# SCH.net
KiCad netlist of a schematic drawn in EasyEDA
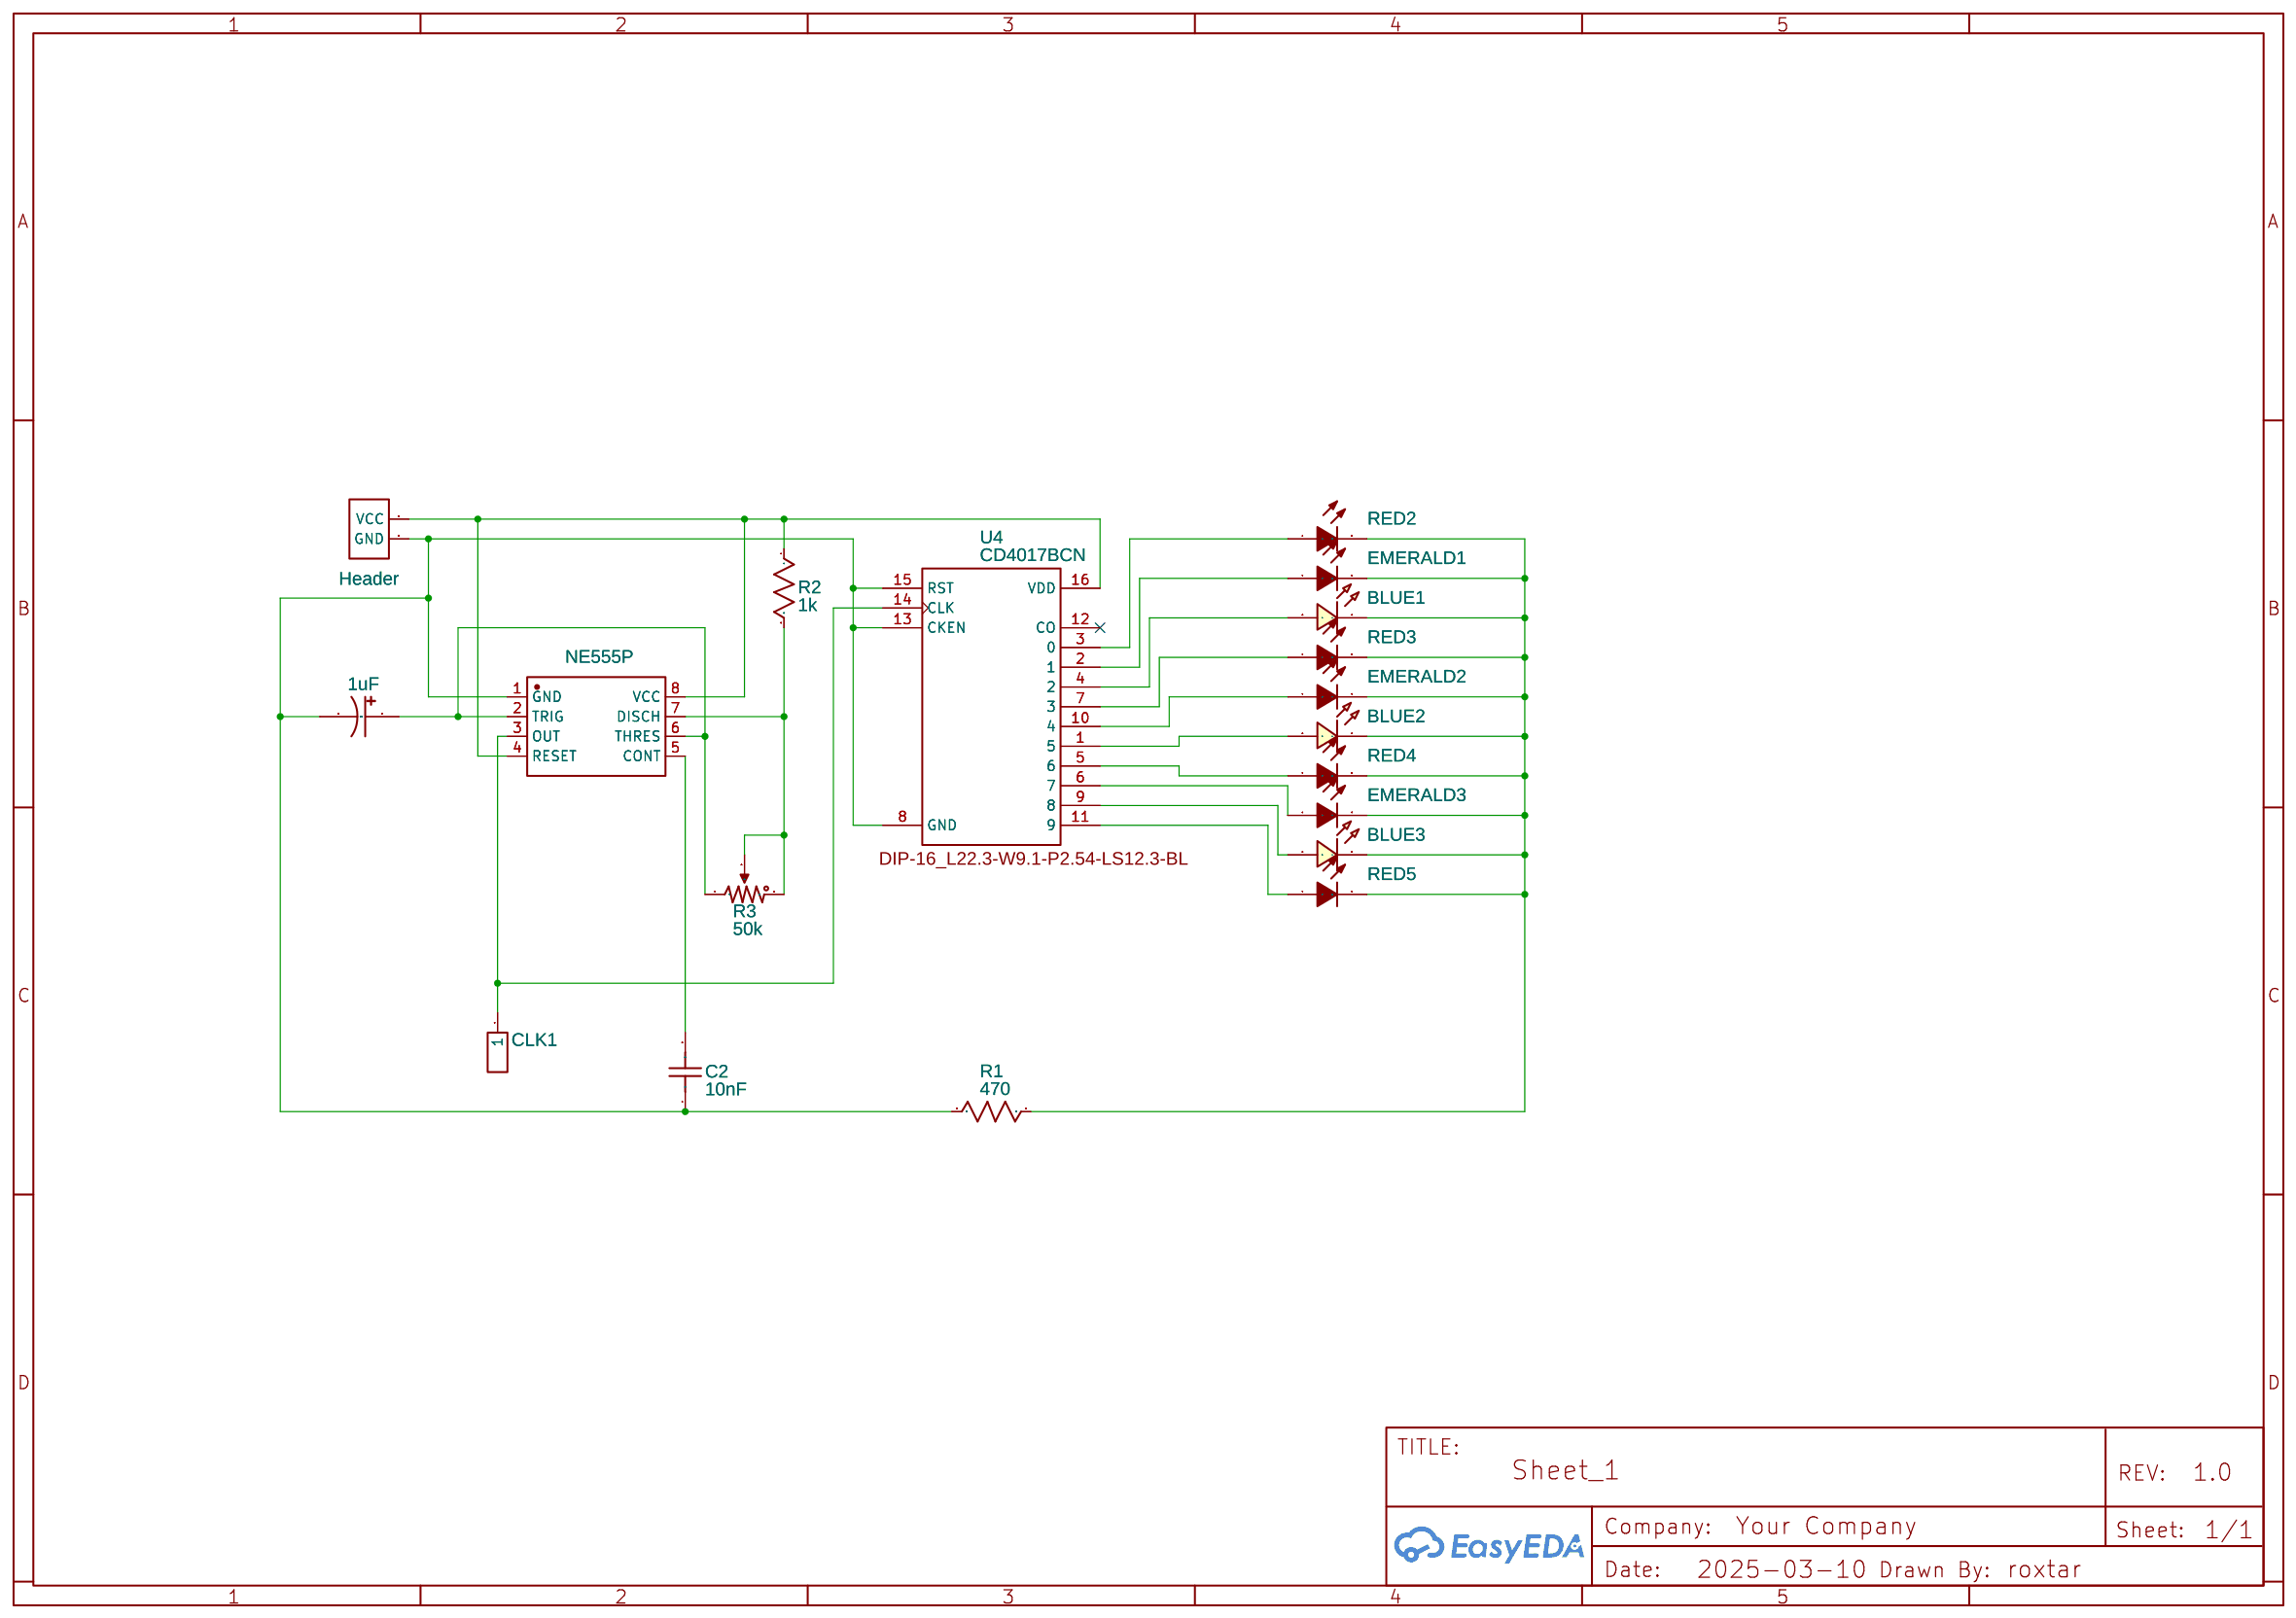
[diagram p0: schematic sheet]

(export (version "E")
  (design (tool "Eeschema 10.0.6"))
  (components
    (comp (ref "BLUE1")
      (value "MHL5013UBDWT")
      (fields (field (name "Manufacturer") "MEIHUA(美华)"))
      (libsource (lib "") (part "MHL5013UBDWT"))
    )
    (comp (ref "BLUE2")
      (value "MHL5013UBDWT")
      (fields (field (name "Manufacturer") "MEIHUA(美华)"))
      (libsource (lib "") (part "MHL5013UBDWT"))
    )
    (comp (ref "BLUE3")
      (value "MHL5013UBDWT")
      (fields (field (name "Manufacturer") "MEIHUA(美华)"))
      (libsource (lib "") (part "MHL5013UBDWT"))
    )
    (comp (ref "C1")
      (value "1uF")
      (fields (field (name "Manufacturer Part") "UVZ1H010MDD") (field (name "Manufacturer") "Nichicon(尼吉康)"))
      (libsource (lib "") (part "UVZ1H010MDD"))
    )
    (comp (ref "C2")
      (value "10nF")
      (fields
        (field (name "Manufacturer Part") "CT41G-0603-2X1-50V-0.01μF-K(N)")
        (field (name "Manufacturer") "TORCH(火炬)")
      )
      (libsource (lib "") (part "CT41G-0603-2X1-50V-0.01UF-K(N)"))
    )
    (comp (ref "CLK1")
      (value "C81276")
      (fields
        (field (name "Manufacturer Part") "2.54-1*1P针")
        (field (name "Manufacturer") "BOOMELE(Boom Precision Elec)")
      )
      (libsource (lib "") (part "Header-Male-2.54_1x1"))
    )
    (comp (ref "EMERALD1") (value "LED_5MM") (libsource (lib "") (part "LED_5MM_1")))
    (comp (ref "EMERALD2") (value "LED_5MM") (libsource (lib "") (part "LED_5MM_1")))
    (comp (ref "EMERALD3") (value "LED_5MM") (libsource (lib "") (part "LED_5MM_1")))
    (comp (ref "H1") (value "Header") (libsource (lib "") (part "HEADER-FEMALE-2.54_1X2")))
    (comp (ref "R1")
      (value "470")
      (fields (field (name "Manufacturer Part") "?"))
      (libsource (lib "") (part "Resistor_1"))
    )
    (comp (ref "R2")
      (value "1k")
      (fields (field (name "Manufacturer Part") "?"))
      (libsource (lib "") (part "Resistor"))
    )
    (comp (ref "R3")
      (value "50k")
      (fields (field (name "Manufacturer Part") "?"))
      (libsource (lib "") (part "Potentiometer"))
    )
    (comp (ref "RED2") (value "LED_5MM") (libsource (lib "") (part "LED_5MM")))
    (comp (ref "RED3") (value "LED_5MM") (libsource (lib "") (part "LED_5MM")))
    (comp (ref "RED4") (value "LED_5MM") (libsource (lib "") (part "LED_5MM")))
    (comp (ref "RED5") (value "LED_5MM") (libsource (lib "") (part "LED_5MM")))
    (comp (ref "U2")
      (value "NE555P")
      (fields (field (name "Manufacturer") "TI(德州仪器)"))
      (libsource (lib "") (part "NE555P"))
    )
    (comp (ref "U4") (value "CD4017BCN") (libsource (lib "") (part "CD4017BCN")))
  )
  (nets
    (net (code "1") (name "Net-(BLUE1-+)") (class "Default")
      (node (ref "BLUE1") (pin "2") (pinfunction "+_2") (pintype "unspecified"))
      (node (ref "U4") (pin "4") (pinfunction "2_4") (pintype "output"))
    )
    (net (code "2") (name "Net-(BLUE1--)") (class "Default")
      (node (ref "BLUE1") (pin "1") (pinfunction "-_1") (pintype "unspecified"))
      (node (ref "BLUE2") (pin "1") (pinfunction "-_1") (pintype "unspecified"))
      (node (ref "BLUE3") (pin "1") (pinfunction "-_1") (pintype "unspecified"))
      (node (ref "EMERALD1") (pin "2") (pinfunction "K_2") (pintype "input"))
      (node (ref "EMERALD2") (pin "2") (pinfunction "K_2") (pintype "input"))
      (node (ref "EMERALD3") (pin "2") (pinfunction "K_2") (pintype "input"))
      (node (ref "R1") (pin "1") (pinfunction "1_1") (pintype "unspecified"))
      (node (ref "RED2") (pin "2") (pinfunction "K_2") (pintype "input"))
      (node (ref "RED3") (pin "2") (pinfunction "K_2") (pintype "input"))
      (node (ref "RED4") (pin "2") (pinfunction "K_2") (pintype "input"))
      (node (ref "RED5") (pin "2") (pinfunction "K_2") (pintype "input"))
    )
    (net (code "3") (name "Net-(BLUE2-+)") (class "Default")
      (node (ref "BLUE2") (pin "2") (pinfunction "+_2") (pintype "unspecified"))
      (node (ref "U4") (pin "1") (pinfunction "5_1") (pintype "output"))
    )
    (net (code "4") (name "Net-(BLUE3-+)") (class "Default")
      (node (ref "BLUE3") (pin "2") (pinfunction "+_2") (pintype "unspecified"))
      (node (ref "U4") (pin "9") (pinfunction "8_9") (pintype "output"))
    )
    (net (code "5") (name "Net-(EMERALD1-A)") (class "Default")
      (node (ref "EMERALD1") (pin "1") (pinfunction "A_1") (pintype "input"))
      (node (ref "U4") (pin "2") (pinfunction "1_2") (pintype "output"))
    )
    (net (code "6") (name "Net-(EMERALD2-A)") (class "Default")
      (node (ref "EMERALD2") (pin "1") (pinfunction "A_1") (pintype "input"))
      (node (ref "U4") (pin "10") (pinfunction "4_10") (pintype "output"))
    )
    (net (code "7") (name "Net-(EMERALD3-A)") (class "Default")
      (node (ref "EMERALD3") (pin "1") (pinfunction "A_1") (pintype "input"))
      (node (ref "U4") (pin "6") (pinfunction "7_6") (pintype "output"))
    )
    (net (code "8") (name "Net-(H1-GND)") (class "Default")
      (node (ref "C1") (pin "2") (pinfunction "2_2") (pintype "unspecified"))
      (node (ref "C2") (pin "1") (pinfunction "1_1") (pintype "unspecified"))
      (node (ref "H1") (pin "2") (pinfunction "GND_2") (pintype "unspecified"))
      (node (ref "R1") (pin "2") (pinfunction "2_2") (pintype "unspecified"))
      (node (ref "U2") (pin "1") (pinfunction "GND_1") (pintype "unspecified"))
      (node (ref "U4") (pin "13") (pinfunction "CKEN_13") (pintype "unspecified"))
      (node (ref "U4") (pin "15") (pinfunction "RST_15") (pintype "unspecified"))
      (node (ref "U4") (pin "8") (pinfunction "GND_8") (pintype "passive"))
    )
    (net (code "9") (name "Net-(H1-VCC)") (class "Default")
      (node (ref "H1") (pin "1") (pinfunction "VCC_1") (pintype "unspecified"))
      (node (ref "R2") (pin "1") (pinfunction "1_1") (pintype "unspecified"))
      (node (ref "U2") (pin "4") (pinfunction "RESET_4") (pintype "unspecified"))
      (node (ref "U2") (pin "8") (pinfunction "VCC_8") (pintype "unspecified"))
      (node (ref "U4") (pin "16") (pinfunction "VDD_16") (pintype "passive"))
    )
    (net (code "10") (name "Net-(R3-2)") (class "Default")
      (node (ref "R2") (pin "2") (pinfunction "2_2") (pintype "unspecified"))
      (node (ref "R3") (pin "2") (pinfunction "3_2") (pintype "unspecified"))
      (node (ref "R3") (pin "3") (pinfunction "2_3") (pintype "unspecified"))
      (node (ref "U2") (pin "7") (pinfunction "DISCH_7") (pintype "unspecified"))
    )
    (net (code "11") (name "Net-(RED2-A)") (class "Default")
      (node (ref "RED2") (pin "1") (pinfunction "A_1") (pintype "input"))
      (node (ref "U4") (pin "3") (pinfunction "0_3") (pintype "output"))
    )
    (net (code "12") (name "Net-(RED3-A)") (class "Default")
      (node (ref "RED3") (pin "1") (pinfunction "A_1") (pintype "input"))
      (node (ref "U4") (pin "7") (pinfunction "3_7") (pintype "output"))
    )
    (net (code "13") (name "Net-(RED4-A)") (class "Default")
      (node (ref "RED4") (pin "1") (pinfunction "A_1") (pintype "input"))
      (node (ref "U4") (pin "5") (pinfunction "6_5") (pintype "output"))
    )
    (net (code "14") (name "Net-(RED5-A)") (class "Default")
      (node (ref "RED5") (pin "1") (pinfunction "A_1") (pintype "input"))
      (node (ref "U4") (pin "11") (pinfunction "9_11") (pintype "output"))
    )
    (net (code "15") (name "Net-(U2-CONT)") (class "Default")
      (node (ref "C2") (pin "2") (pinfunction "2_2") (pintype "unspecified"))
      (node (ref "U2") (pin "5") (pinfunction "CONT_5") (pintype "unspecified"))
    )
    (net (code "16") (name "Net-(U2-OUT)") (class "Default")
      (node (ref "CLK1") (pin "1") (pinfunction "1_1") (pintype "unspecified"))
      (node (ref "U2") (pin "3") (pinfunction "OUT_3") (pintype "unspecified"))
      (node (ref "U4") (pin "14") (pinfunction "CLK_14") (pintype "unspecified"))
    )
    (net (code "17") (name "Net-(U2-THRES)") (class "Default")
      (node (ref "C1") (pin "1") (pinfunction "1_1") (pintype "unspecified"))
      (node (ref "R3") (pin "1") (pinfunction "1_1") (pintype "unspecified"))
      (node (ref "U2") (pin "2") (pinfunction "TRIG_2") (pintype "unspecified"))
      (node (ref "U2") (pin "6") (pinfunction "THRES_6") (pintype "unspecified"))
    )
    (net (code "18") (name "unconnected-(U4-CO-Pad12)") (class "Default")
      (node (ref "U4") (pin "12") (pinfunction "CO_12") (pintype "output+no_connect"))
    )
  )
)
